# Outputs.net
KiCad netlist of a schematic drawn in Altium Designer
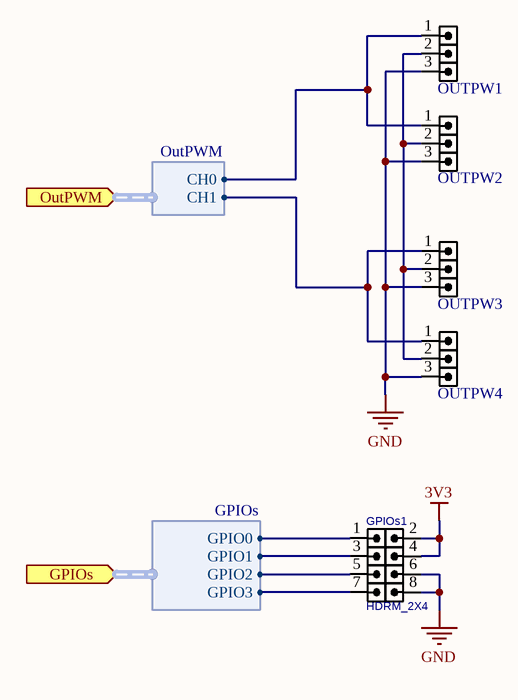
[diagram p0: Outputs.SchDoc]

(export (version "E")
  (design (tool "Eeschema 10.0.6"))
  (components
    (comp (ref "GPIOs1")
      (value "HDRM_2X4")
      (footprint "HDR_M_2X4")
      (description "CONN, HEADER, Male, pitch: 2.54mm, 8POS")
      (fields (field (name "MANF_P#") "MANF_PART#") (field (name "MANF") "MANF"))
      (libsource (lib "Conn Header") (part "HDR_M_2X4"))
    )
    (comp (ref "OUTPW1")
      (value "HDRM3")
      (footprint "HDR_M_1X3")
      (description "CONN, HEADER, Male, pitch: 2.54mm, 3POS")
      (libsource (lib "Conn Header") (part "HDR_M_1X3"))
    )
    (comp (ref "OUTPW2")
      (value "HDRM3")
      (footprint "HDR_M_1X3")
      (description "CONN, HEADER, Male, pitch: 2.54mm, 3POS")
      (libsource (lib "Conn Header") (part "HDR_M_1X3"))
    )
    (comp (ref "OUTPW3")
      (value "HDRM3")
      (footprint "HDR_M_1X3")
      (description "CONN, HEADER, Male, pitch: 2.54mm, 3POS")
      (libsource (lib "Conn Header") (part "HDR_M_1X3"))
    )
    (comp (ref "OUTPW4")
      (value "HDRM3")
      (footprint "HDR_M_1X3")
      (description "CONN, HEADER, Male, pitch: 2.54mm, 3POS")
      (libsource (lib "Conn Header") (part "HDR_M_1X3"))
    )
  )
  (nets
    (net (code "3") (name "/CH0") (class "Default")
      (node (ref "OUTPW1") (pin "1") (pinfunction "1_1") (pintype "passive"))
      (node (ref "OUTPW2") (pin "1") (pinfunction "1_1") (pintype "passive"))
    )
    (net (code "4") (name "/CH1") (class "Default")
      (node (ref "OUTPW3") (pin "1") (pinfunction "1_1") (pintype "passive"))
      (node (ref "OUTPW4") (pin "1") (pinfunction "1_1") (pintype "passive"))
    )
    (net (code "5") (name "/GPIO0") (class "Default")
      (node (ref "GPIOs1") (pin "1") (pinfunction "1_1") (pintype "passive"))
    )
    (net (code "6") (name "/GPIO1") (class "Default")
      (node (ref "GPIOs1") (pin "3") (pinfunction "3_3") (pintype "passive"))
    )
    (net (code "7") (name "/GPIO2") (class "Default")
      (node (ref "GPIOs1") (pin "5") (pinfunction "5_5") (pintype "passive"))
    )
    (net (code "8") (name "/GPIO3") (class "Default")
      (node (ref "GPIOs1") (pin "7") (pinfunction "7_7") (pintype "passive"))
    )
    (net (code "11") (name "3V3") (class "Default")
      (node (ref "GPIOs1") (pin "2") (pinfunction "2_2") (pintype "passive"))
      (node (ref "GPIOs1") (pin "4") (pinfunction "4_4") (pintype "passive"))
    )
    (net (code "12") (name "GND") (class "Default")
      (node (ref "GPIOs1") (pin "6") (pinfunction "6_6") (pintype "passive"))
      (node (ref "GPIOs1") (pin "8") (pinfunction "8_8") (pintype "passive"))
      (node (ref "OUTPW1") (pin "3") (pinfunction "3_3") (pintype "passive"))
      (node (ref "OUTPW2") (pin "3") (pinfunction "3_3") (pintype "passive"))
      (node (ref "OUTPW3") (pin "3") (pinfunction "3_3") (pintype "passive"))
      (node (ref "OUTPW4") (pin "3") (pinfunction "3_3") (pintype "passive"))
    )
    (net (code "13") (name "Net-(OUTPW1-Pad2)") (class "Default")
      (node (ref "OUTPW1") (pin "2") (pinfunction "2_2") (pintype "passive"))
      (node (ref "OUTPW2") (pin "2") (pinfunction "2_2") (pintype "passive"))
      (node (ref "OUTPW3") (pin "2") (pinfunction "2_2") (pintype "passive"))
      (node (ref "OUTPW4") (pin "2") (pinfunction "2_2") (pintype "passive"))
    )
  )
)
